# SAMD11_Arduino_Small_Form_Factor.net
KiCad netlist of a schematic drawn in EAGLE
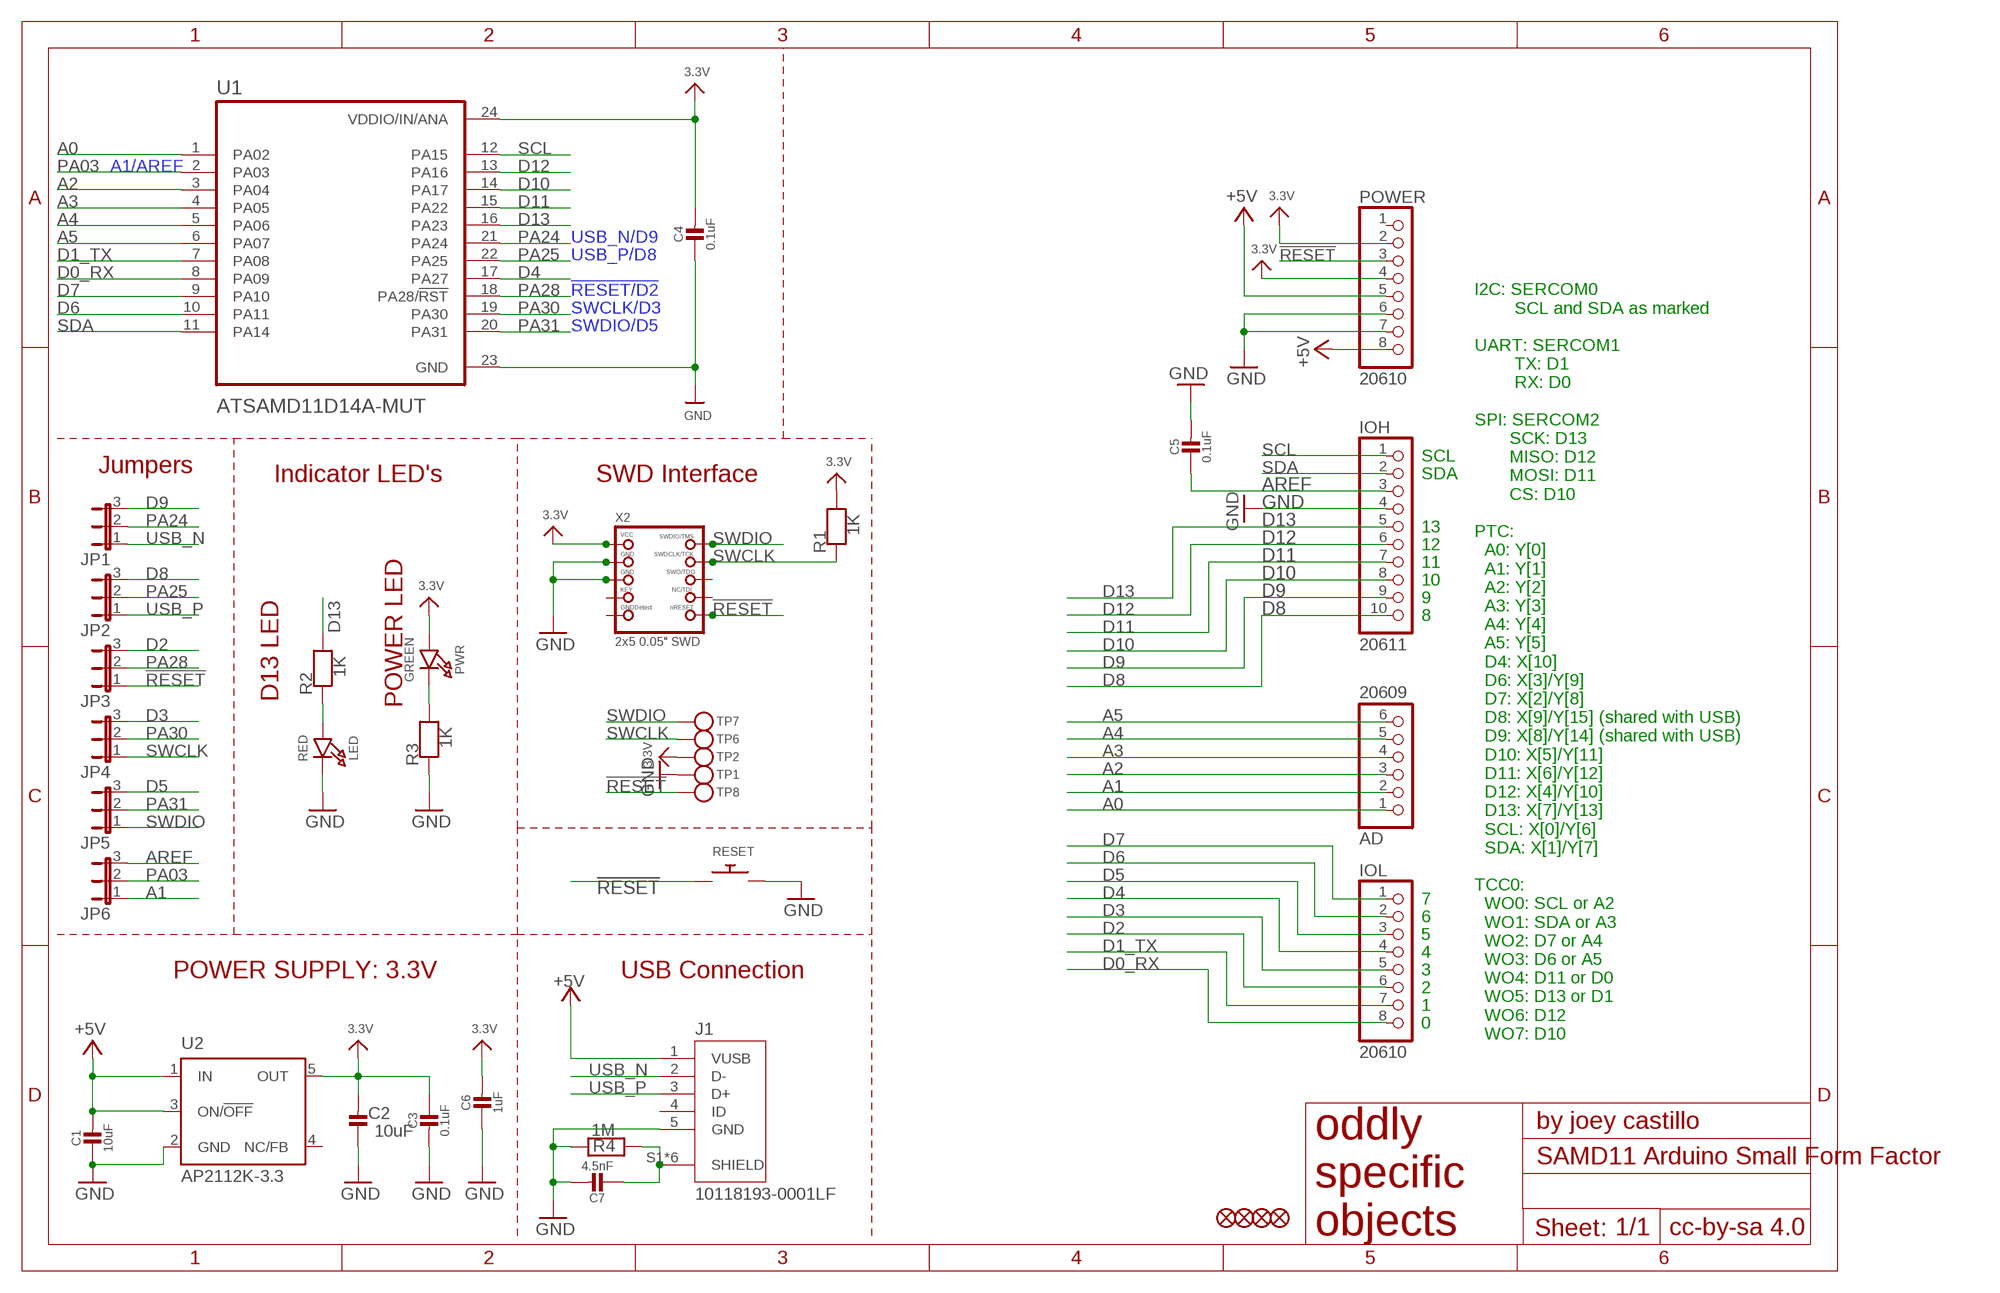
[diagram p0: schematic, sheet 1, part 1 of 2]
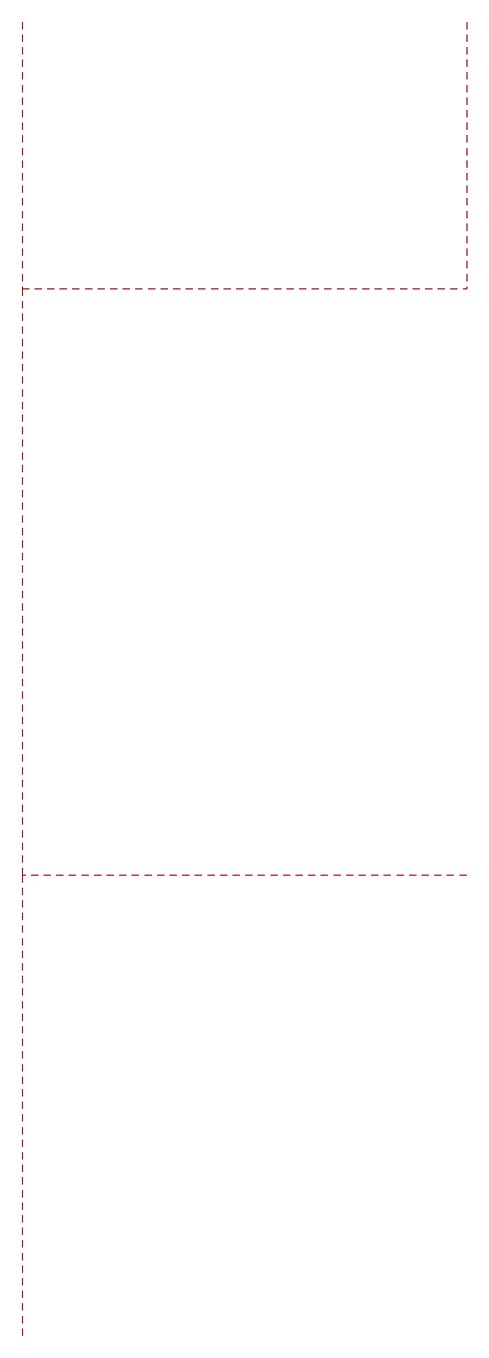
[diagram p1: schematic, sheet 1, part 2 of 2]

(export (version "E")
  (design (tool "Eeschema 10.0.6"))
  (components
    (comp (ref "AD")
      (value "20609")
      (footprint "eagle-import:1X06_OVALWAVE")
      (libsource (lib "eagle-import") (part "HEADER-1X6OVALWAVE"))
    )
    (comp (ref "C1")
      (value "10uF")
      (footprint "eagle-import:0805-NO")
      (libsource (lib "eagle-import") (part "CAP_CERAMIC0805-NOOUTLINE"))
    )
    (comp (ref "C2")
      (value "10uF")
      (footprint "eagle-import:0805-NO")
      (libsource (lib "eagle-import") (part "CAP_CERAMIC0805-NOOUTLINE"))
    )
    (comp (ref "C3")
      (value "0.1uF")
      (footprint "eagle-import:0805-NO")
      (libsource (lib "eagle-import") (part "CAP_CERAMIC0805-NOOUTLINE"))
    )
    (comp (ref "C4")
      (value "0.1uF")
      (footprint "eagle-import:0805-NO")
      (libsource (lib "eagle-import") (part "CAP_CERAMIC0805-NOOUTLINE"))
    )
    (comp (ref "C5")
      (value "0.1uF")
      (footprint "eagle-import:0805-NO")
      (libsource (lib "eagle-import") (part "CAP_CERAMIC0805-NOOUTLINE"))
    )
    (comp (ref "C6")
      (value "1uF")
      (footprint "eagle-import:0805-NO")
      (libsource (lib "eagle-import") (part "CAP_CERAMIC0805-NOOUTLINE"))
    )
    (comp (ref "C7")
      (value "4.5nF")
      (footprint "eagle-import:0805-NO")
      (libsource (lib "eagle-import") (part "CAP_CERAMIC0805-NOOUTLINE"))
    )
    (comp (ref "FD1")
      (value "FIDUCIAL_1MM")
      (footprint "eagle-import:FIDUCIAL_1MM")
      (libsource (lib "eagle-import") (part "FIDUCIAL_1MM"))
    )
    (comp (ref "FD2")
      (value "FIDUCIAL_1MM")
      (footprint "eagle-import:FIDUCIAL_1MM")
      (libsource (lib "eagle-import") (part "FIDUCIAL_1MM"))
    )
    (comp (ref "FD3")
      (value "FIDUCIAL_1MM")
      (footprint "eagle-import:FIDUCIAL_1MM")
      (libsource (lib "eagle-import") (part "FIDUCIAL_1MM"))
    )
    (comp (ref "FD4")
      (value "FIDUCIAL_1MM")
      (footprint "eagle-import:FIDUCIAL_1MM")
      (libsource (lib "eagle-import") (part "FIDUCIAL_1MM"))
    )
    (comp (ref "IOH")
      (value "20611")
      (footprint "eagle-import:1X10_OVALWAVE")
      (libsource (lib "eagle-import") (part "HEADER-1X10OVALWAVE"))
    )
    (comp (ref "IOL")
      (value "20610")
      (footprint "eagle-import:1X08_OVALWAVE")
      (libsource (lib "eagle-import") (part "HEADER-1X8OVALWAVE"))
    )
    (comp (ref "J1")
      (value "10118193-0001LF")
      (footprint "eagle-import:FCI_10118193-0001LF")
      (fields (field (name "DIGI-KEY_PART_NUMBER") "609-4616-1-ND") (field (name "MF") "Amphenol ICC"))
      (libsource (lib "eagle-import") (part "10118193-0001LF"))
    )
    (comp (ref "JP1")
      (value "JP2E")
      (footprint "eagle-import:JP2")
      (libsource (lib "eagle-import") (part "JP2E"))
    )
    (comp (ref "JP2")
      (value "JP2E")
      (footprint "eagle-import:JP2")
      (libsource (lib "eagle-import") (part "JP2E"))
    )
    (comp (ref "JP3")
      (value "JP2E")
      (footprint "eagle-import:JP2")
      (libsource (lib "eagle-import") (part "JP2E"))
    )
    (comp (ref "JP4")
      (value "JP2E")
      (footprint "eagle-import:JP2")
      (libsource (lib "eagle-import") (part "JP2E"))
    )
    (comp (ref "JP5")
      (value "JP2E")
      (footprint "eagle-import:JP2")
      (libsource (lib "eagle-import") (part "JP2E"))
    )
    (comp (ref "JP6")
      (value "JP2E")
      (footprint "eagle-import:JP2")
      (libsource (lib "eagle-import") (part "JP2E"))
    )
    (comp (ref "LED")
      (value "RED")
      (footprint "eagle-import:CHIPLED_0805_NOOUTLINE")
      (libsource (lib "eagle-import") (part "LED0805_NOOUTLINE"))
    )
    (comp (ref "POWER")
      (value "20610")
      (footprint "eagle-import:1X08_OVALWAVE")
      (libsource (lib "eagle-import") (part "HEADER-1X8OVALWAVE"))
    )
    (comp (ref "PWR")
      (value "GREEN")
      (footprint "eagle-import:CHIPLED_0805_NOOUTLINE")
      (libsource (lib "eagle-import") (part "LED0805_NOOUTLINE"))
    )
    (comp (ref "R1")
      (value "1K")
      (footprint "eagle-import:0805-NO")
      (libsource (lib "eagle-import") (part "RESISTOR0805_NOOUTLINE"))
    )
    (comp (ref "R2")
      (value "1K")
      (footprint "eagle-import:0805-NO")
      (libsource (lib "eagle-import") (part "RESISTOR0805_NOOUTLINE"))
    )
    (comp (ref "R3")
      (value "1K")
      (footprint "eagle-import:0805-NO")
      (libsource (lib "eagle-import") (part "RESISTOR0805_NOOUTLINE"))
    )
    (comp (ref "R4")
      (value "1M")
      (footprint "eagle-import:0805-NO")
      (libsource (lib "eagle-import") (part "RESISTOR0805_NOOUTLINE"))
    )
    (comp (ref "RESET")
      (value "SWITCH_PUSHBUTTONEVQ-PE")
      (footprint "eagle-import:TACT_PANA-EVQ")
      (libsource (lib "eagle-import") (part "SWITCH_PUSHBUTTONEVQ-PE"))
    )
    (comp (ref "TP1")
      (value "TESTPOINTROUND2MMNO")
      (footprint "eagle-import:TESTPOINT_ROUND_2MM_NO")
      (libsource (lib "eagle-import") (part "TESTPOINTROUND2MMNO"))
    )
    (comp (ref "TP2")
      (value "TESTPOINTROUND2MMNO")
      (footprint "eagle-import:TESTPOINT_ROUND_2MM_NO")
      (libsource (lib "eagle-import") (part "TESTPOINTROUND2MMNO"))
    )
    (comp (ref "TP6")
      (value "TESTPOINTROUND2MMNO")
      (footprint "eagle-import:TESTPOINT_ROUND_2MM_NO")
      (libsource (lib "eagle-import") (part "TESTPOINTROUND2MMNO"))
    )
    (comp (ref "TP7")
      (value "TESTPOINTROUND2MMNO")
      (footprint "eagle-import:TESTPOINT_ROUND_2MM_NO")
      (libsource (lib "eagle-import") (part "TESTPOINTROUND2MMNO"))
    )
    (comp (ref "TP8")
      (value "TESTPOINTROUND2MMNO")
      (footprint "eagle-import:TESTPOINT_ROUND_2MM_NO")
      (libsource (lib "eagle-import") (part "TESTPOINTROUND2MMNO"))
    )
    (comp (ref "U1")
      (value "ATSAMD11D14A-MUT")
      (footprint "eagle-import:QFN50P400X400X90-25N")
      (fields (field (name "MF") "Microchip"))
      (libsource (lib "eagle-import") (part "ATSAMD11D14A-MUT"))
    )
    (comp (ref "U2")
      (value "AP2112K-3.3")
      (footprint "eagle-import:SOT23-DBV")
      (libsource (lib "eagle-import") (part "LP2985-XXDBVR33"))
    )
    (comp (ref "X2")
      (value "2x5 0.05\" SWD")
      (footprint "eagle-import:2X05_1.27MM_BOX_POSTS")
      (libsource (lib "eagle-import") (part "JTAG-CORTEXBOXPOSTS"))
    )
  )
  (nets
    (net (code "1") (name "+5V") (class "Default")
      (node (ref "C1") (pin "2") (pinfunction "2_2") (pintype "passive"))
      (node (ref "J1") (pin "1") (pinfunction "VUSB_1") (pintype "passive"))
      (node (ref "POWER") (pin "5") (pinfunction "5_5") (pintype "passive"))
      (node (ref "POWER") (pin "8") (pinfunction "8_8") (pintype "passive"))
      (node (ref "U2") (pin "1") (pinfunction "IN_1") (pintype "input"))
      (node (ref "U2") (pin "3") (pinfunction "ON/~{OFF}_3") (pintype "input"))
    )
    (net (code "2") (name "/A0") (class "Default")
      (node (ref "AD") (pin "1") (pinfunction "1_1") (pintype "passive"))
      (node (ref "U1") (pin "1") (pinfunction "PA02_1") (pintype "bidirectional"))
    )
    (net (code "3") (name "/A1") (class "Default")
      (node (ref "AD") (pin "2") (pinfunction "2_2") (pintype "passive"))
      (node (ref "JP6") (pin "1") (pinfunction "1_1") (pintype "passive"))
    )
    (net (code "4") (name "/A2") (class "Default")
      (node (ref "AD") (pin "3") (pinfunction "3_3") (pintype "passive"))
      (node (ref "U1") (pin "3") (pinfunction "PA04_3") (pintype "bidirectional"))
    )
    (net (code "5") (name "/A3") (class "Default")
      (node (ref "AD") (pin "4") (pinfunction "4_4") (pintype "passive"))
      (node (ref "U1") (pin "4") (pinfunction "PA05_4") (pintype "bidirectional"))
    )
    (net (code "6") (name "/A4") (class "Default")
      (node (ref "AD") (pin "5") (pinfunction "5_5") (pintype "passive"))
      (node (ref "U1") (pin "5") (pinfunction "PA06_5") (pintype "bidirectional"))
    )
    (net (code "7") (name "/A5") (class "Default")
      (node (ref "AD") (pin "6") (pinfunction "6_6") (pintype "passive"))
      (node (ref "U1") (pin "6") (pinfunction "PA07_6") (pintype "bidirectional"))
    )
    (net (code "8") (name "/AREF") (class "Default")
      (node (ref "C5") (pin "1") (pinfunction "1_1") (pintype "passive"))
      (node (ref "IOH") (pin "3") (pinfunction "3_3") (pintype "passive"))
      (node (ref "JP6") (pin "3") (pinfunction "3_3") (pintype "passive"))
    )
    (net (code "9") (name "/D0_RX") (class "Default")
      (node (ref "IOL") (pin "8") (pinfunction "8_8") (pintype "passive"))
      (node (ref "U1") (pin "8") (pinfunction "PA09_8") (pintype "bidirectional"))
    )
    (net (code "10") (name "/D1_TX") (class "Default")
      (node (ref "IOL") (pin "7") (pinfunction "7_7") (pintype "passive"))
      (node (ref "U1") (pin "7") (pinfunction "PA08_7") (pintype "bidirectional"))
    )
    (net (code "11") (name "/D2") (class "Default")
      (node (ref "IOL") (pin "6") (pinfunction "6_6") (pintype "passive"))
      (node (ref "JP3") (pin "3") (pinfunction "3_3") (pintype "passive"))
    )
    (net (code "12") (name "/D3") (class "Default")
      (node (ref "IOL") (pin "5") (pinfunction "5_5") (pintype "passive"))
      (node (ref "JP4") (pin "3") (pinfunction "3_3") (pintype "passive"))
    )
    (net (code "13") (name "/D4") (class "Default")
      (node (ref "IOL") (pin "4") (pinfunction "4_4") (pintype "passive"))
      (node (ref "U1") (pin "17") (pinfunction "PA27_17") (pintype "bidirectional"))
    )
    (net (code "14") (name "/D5") (class "Default")
      (node (ref "IOL") (pin "3") (pinfunction "3_3") (pintype "passive"))
      (node (ref "JP5") (pin "3") (pinfunction "3_3") (pintype "passive"))
    )
    (net (code "15") (name "/D6") (class "Default")
      (node (ref "IOL") (pin "2") (pinfunction "2_2") (pintype "passive"))
      (node (ref "U1") (pin "10") (pinfunction "PA11_10") (pintype "bidirectional"))
    )
    (net (code "16") (name "/D7") (class "Default")
      (node (ref "IOL") (pin "1") (pinfunction "1_1") (pintype "passive"))
      (node (ref "U1") (pin "9") (pinfunction "PA10_9") (pintype "bidirectional"))
    )
    (net (code "17") (name "/D8") (class "Default")
      (node (ref "IOH") (pin "10") (pinfunction "10_10") (pintype "passive"))
      (node (ref "JP2") (pin "3") (pinfunction "3_3") (pintype "passive"))
    )
    (net (code "18") (name "/D9") (class "Default")
      (node (ref "IOH") (pin "9") (pinfunction "9_9") (pintype "passive"))
      (node (ref "JP1") (pin "3") (pinfunction "3_3") (pintype "passive"))
    )
    (net (code "19") (name "/D10") (class "Default")
      (node (ref "IOH") (pin "8") (pinfunction "8_8") (pintype "passive"))
      (node (ref "U1") (pin "14") (pinfunction "PA17_14") (pintype "bidirectional"))
    )
    (net (code "20") (name "/D11") (class "Default")
      (node (ref "IOH") (pin "7") (pinfunction "7_7") (pintype "passive"))
      (node (ref "U1") (pin "15") (pinfunction "PA22_15") (pintype "bidirectional"))
    )
    (net (code "21") (name "/D12") (class "Default")
      (node (ref "IOH") (pin "6") (pinfunction "6_6") (pintype "passive"))
      (node (ref "U1") (pin "13") (pinfunction "PA16_13") (pintype "bidirectional"))
    )
    (net (code "22") (name "/D13") (class "Default")
      (node (ref "IOH") (pin "5") (pinfunction "5_5") (pintype "passive"))
      (node (ref "R2") (pin "2") (pinfunction "2_2") (pintype "passive"))
      (node (ref "U1") (pin "16") (pinfunction "PA23_16") (pintype "bidirectional"))
    )
    (net (code "23") (name "/PA03") (class "Default")
      (node (ref "JP6") (pin "2") (pinfunction "2_2") (pintype "passive"))
      (node (ref "U1") (pin "2") (pinfunction "PA03_2") (pintype "bidirectional"))
    )
    (net (code "24") (name "/PA24") (class "Default")
      (node (ref "JP1") (pin "2") (pinfunction "2_2") (pintype "passive"))
      (node (ref "U1") (pin "21") (pinfunction "PA24_21") (pintype "bidirectional"))
    )
    (net (code "25") (name "/PA25") (class "Default")
      (node (ref "JP2") (pin "2") (pinfunction "2_2") (pintype "passive"))
      (node (ref "U1") (pin "22") (pinfunction "PA25_22") (pintype "bidirectional"))
    )
    (net (code "26") (name "/PA28") (class "Default")
      (node (ref "JP3") (pin "2") (pinfunction "2_2") (pintype "passive"))
      (node (ref "U1") (pin "18") (pinfunction "PA28/~{RST}_18") (pintype "bidirectional"))
    )
    (net (code "27") (name "/PA30") (class "Default")
      (node (ref "JP4") (pin "2") (pinfunction "2_2") (pintype "passive"))
      (node (ref "U1") (pin "19") (pinfunction "PA30_19") (pintype "bidirectional"))
    )
    (net (code "28") (name "/PA31") (class "Default")
      (node (ref "JP5") (pin "2") (pinfunction "2_2") (pintype "passive"))
      (node (ref "U1") (pin "20") (pinfunction "PA31_20") (pintype "bidirectional"))
    )
    (net (code "29") (name "/SCL") (class "Default")
      (node (ref "IOH") (pin "1") (pinfunction "1_1") (pintype "passive"))
      (node (ref "U1") (pin "12") (pinfunction "PA15_12") (pintype "bidirectional"))
    )
    (net (code "30") (name "/SDA") (class "Default")
      (node (ref "IOH") (pin "2") (pinfunction "2_2") (pintype "passive"))
      (node (ref "U1") (pin "11") (pinfunction "PA14_11") (pintype "bidirectional"))
    )
    (net (code "31") (name "/SWCLK") (class "Default")
      (node (ref "JP4") (pin "1") (pinfunction "1_1") (pintype "passive"))
      (node (ref "R1") (pin "1") (pinfunction "1_1") (pintype "passive"))
      (node (ref "TP6") (pin "P$1") (pinfunction "P$1_P$1") (pintype "bidirectional"))
      (node (ref "X2") (pin "4") (pinfunction "SWDCLK_4") (pintype "bidirectional"))
    )
    (net (code "32") (name "/SWDIO") (class "Default")
      (node (ref "JP5") (pin "1") (pinfunction "1_1") (pintype "passive"))
      (node (ref "TP7") (pin "P$1") (pinfunction "P$1_P$1") (pintype "bidirectional"))
      (node (ref "X2") (pin "2") (pinfunction "SWDIO_2") (pintype "bidirectional"))
    )
    (net (code "33") (name "/USB_N") (class "Default")
      (node (ref "J1") (pin "2") (pinfunction "D-_2") (pintype "passive"))
      (node (ref "JP1") (pin "1") (pinfunction "1_1") (pintype "passive"))
    )
    (net (code "34") (name "/USB_P") (class "Default")
      (node (ref "J1") (pin "3") (pinfunction "D+_3") (pintype "passive"))
      (node (ref "JP2") (pin "1") (pinfunction "1_1") (pintype "passive"))
    )
    (net (code "35") (name "/~{RESET}") (class "Default")
      (node (ref "JP3") (pin "1") (pinfunction "1_1") (pintype "passive"))
      (node (ref "POWER") (pin "3") (pinfunction "3_3") (pintype "passive"))
      (node (ref "RESET") (pin "P$1") (pinfunction "P$1_P$1") (pintype "passive"))
      (node (ref "TP8") (pin "P$1") (pinfunction "P$1_P$1") (pintype "bidirectional"))
      (node (ref "X2") (pin "10") (pinfunction "NRESET_10") (pintype "bidirectional"))
    )
    (net (code "36") (name "3.3V") (class "Default")
      (node (ref "C2") (pin "2") (pinfunction "2_2") (pintype "passive"))
      (node (ref "C3") (pin "1") (pinfunction "1_1") (pintype "passive"))
      (node (ref "C4") (pin "2") (pinfunction "2_2") (pintype "passive"))
      (node (ref "C6") (pin "2") (pinfunction "2_2") (pintype "passive"))
      (node (ref "POWER") (pin "2") (pinfunction "2_2") (pintype "passive"))
      (node (ref "POWER") (pin "4") (pinfunction "4_4") (pintype "passive"))
      (node (ref "PWR") (pin "A") (pinfunction "A_A") (pintype "passive"))
      (node (ref "R1") (pin "2") (pinfunction "2_2") (pintype "passive"))
      (node (ref "TP2") (pin "P$1") (pinfunction "P$1_P$1") (pintype "bidirectional"))
      (node (ref "U1") (pin "24") (pinfunction "VDDIO/IN/ANA_24") (pintype "power_in"))
      (node (ref "U2") (pin "5") (pinfunction "OUT_5") (pintype "passive"))
      (node (ref "X2") (pin "1") (pinfunction "VCC_1") (pintype "power_in"))
    )
    (net (code "37") (name "GND") (class "Default")
      (node (ref "C1") (pin "1") (pinfunction "1_1") (pintype "passive"))
      (node (ref "C2") (pin "1") (pinfunction "1_1") (pintype "passive"))
      (node (ref "C3") (pin "2") (pinfunction "2_2") (pintype "passive"))
      (node (ref "C4") (pin "1") (pinfunction "1_1") (pintype "passive"))
      (node (ref "C5") (pin "2") (pinfunction "2_2") (pintype "passive"))
      (node (ref "C6") (pin "1") (pinfunction "1_1") (pintype "passive"))
      (node (ref "C7") (pin "2") (pinfunction "2_2") (pintype "passive"))
      (node (ref "IOH") (pin "4") (pinfunction "4_4") (pintype "passive"))
      (node (ref "J1") (pin "5") (pinfunction "GND_5") (pintype "passive"))
      (node (ref "LED") (pin "C") (pinfunction "C_C") (pintype "passive"))
      (node (ref "POWER") (pin "6") (pinfunction "6_6") (pintype "passive"))
      (node (ref "POWER") (pin "7") (pinfunction "7_7") (pintype "passive"))
      (node (ref "R3") (pin "1") (pinfunction "1_1") (pintype "passive"))
      (node (ref "R4") (pin "2") (pinfunction "2_2") (pintype "passive"))
      (node (ref "RESET") (pin "P$2") (pinfunction "P$2_P$2") (pintype "passive"))
      (node (ref "TP1") (pin "P$1") (pinfunction "P$1_P$1") (pintype "bidirectional"))
      (node (ref "U1") (pin "23") (pinfunction "GND_23") (pintype "power_in"))
      (node (ref "U2") (pin "2") (pinfunction "GND_2") (pintype "power_in"))
      (node (ref "X2") (pin "3") (pinfunction "GND_3") (pintype "power_in"))
      (node (ref "X2") (pin "5") (pinfunction "GND_5") (pintype "power_in"))
    )
    (net (code "38") (name "Net-(C7-Pad1)") (class "Default")
      (node (ref "C7") (pin "1") (pinfunction "1_1") (pintype "passive"))
      (node (ref "J1") (pin "S1") (pinfunction "SHIELD_S1") (pintype "passive"))
      (node (ref "J1") (pin "S2") (pinfunction "SHIELD_S2") (pintype "passive"))
      (node (ref "J1") (pin "S3") (pinfunction "SHIELD_S3") (pintype "passive"))
      (node (ref "J1") (pin "S4") (pinfunction "SHIELD_S4") (pintype "passive"))
      (node (ref "J1") (pin "S5") (pinfunction "SHIELD_S5") (pintype "passive"))
      (node (ref "J1") (pin "S6") (pinfunction "SHIELD_S6") (pintype "passive"))
      (node (ref "R4") (pin "1") (pinfunction "1_1") (pintype "passive"))
    )
    (net (code "39") (name "Net-(LED-PadA)") (class "Default")
      (node (ref "LED") (pin "A") (pinfunction "A_A") (pintype "passive"))
      (node (ref "R2") (pin "1") (pinfunction "1_1") (pintype "passive"))
    )
    (net (code "40") (name "Net-(PWR-PadC)") (class "Default")
      (node (ref "PWR") (pin "C") (pinfunction "C_C") (pintype "passive"))
      (node (ref "R3") (pin "2") (pinfunction "2_2") (pintype "passive"))
    )
    (net (code "41") (name "unconnected-(J1-ID-Pad4)") (class "Default")
      (node (ref "J1") (pin "4") (pinfunction "ID_4") (pintype "passive"))
    )
    (net (code "42") (name "unconnected-(POWER-Pad1)") (class "Default")
      (node (ref "POWER") (pin "1") (pinfunction "1_1") (pintype "passive"))
    )
    (net (code "43") (name "unconnected-(U2-NC{slash}FB-Pad4)") (class "Default")
      (node (ref "U2") (pin "4") (pinfunction "NC/FB_4") (pintype "passive"))
    )
    (net (code "44") (name "unconnected-(X2-GNDDETECT-Pad9)") (class "Default")
      (node (ref "X2") (pin "9") (pinfunction "GNDDETECT_9") (pintype "bidirectional"))
    )
    (net (code "45") (name "unconnected-(X2-KEY-Pad7)") (class "Default")
      (node (ref "X2") (pin "7") (pinfunction "KEY_7") (pintype "bidirectional"))
    )
    (net (code "46") (name "unconnected-(X2-SWO-Pad6)") (class "Default")
      (node (ref "X2") (pin "6") (pinfunction "SWO_6") (pintype "bidirectional"))
    )
    (net (code "47") (name "unconnected-(X2-TDI-Pad8)") (class "Default")
      (node (ref "X2") (pin "8") (pinfunction "TDI_8") (pintype "bidirectional"))
    )
  )
)
